# Water_ECMeter-M0.net
KiCad netlist of a schematic drawn in EAGLE
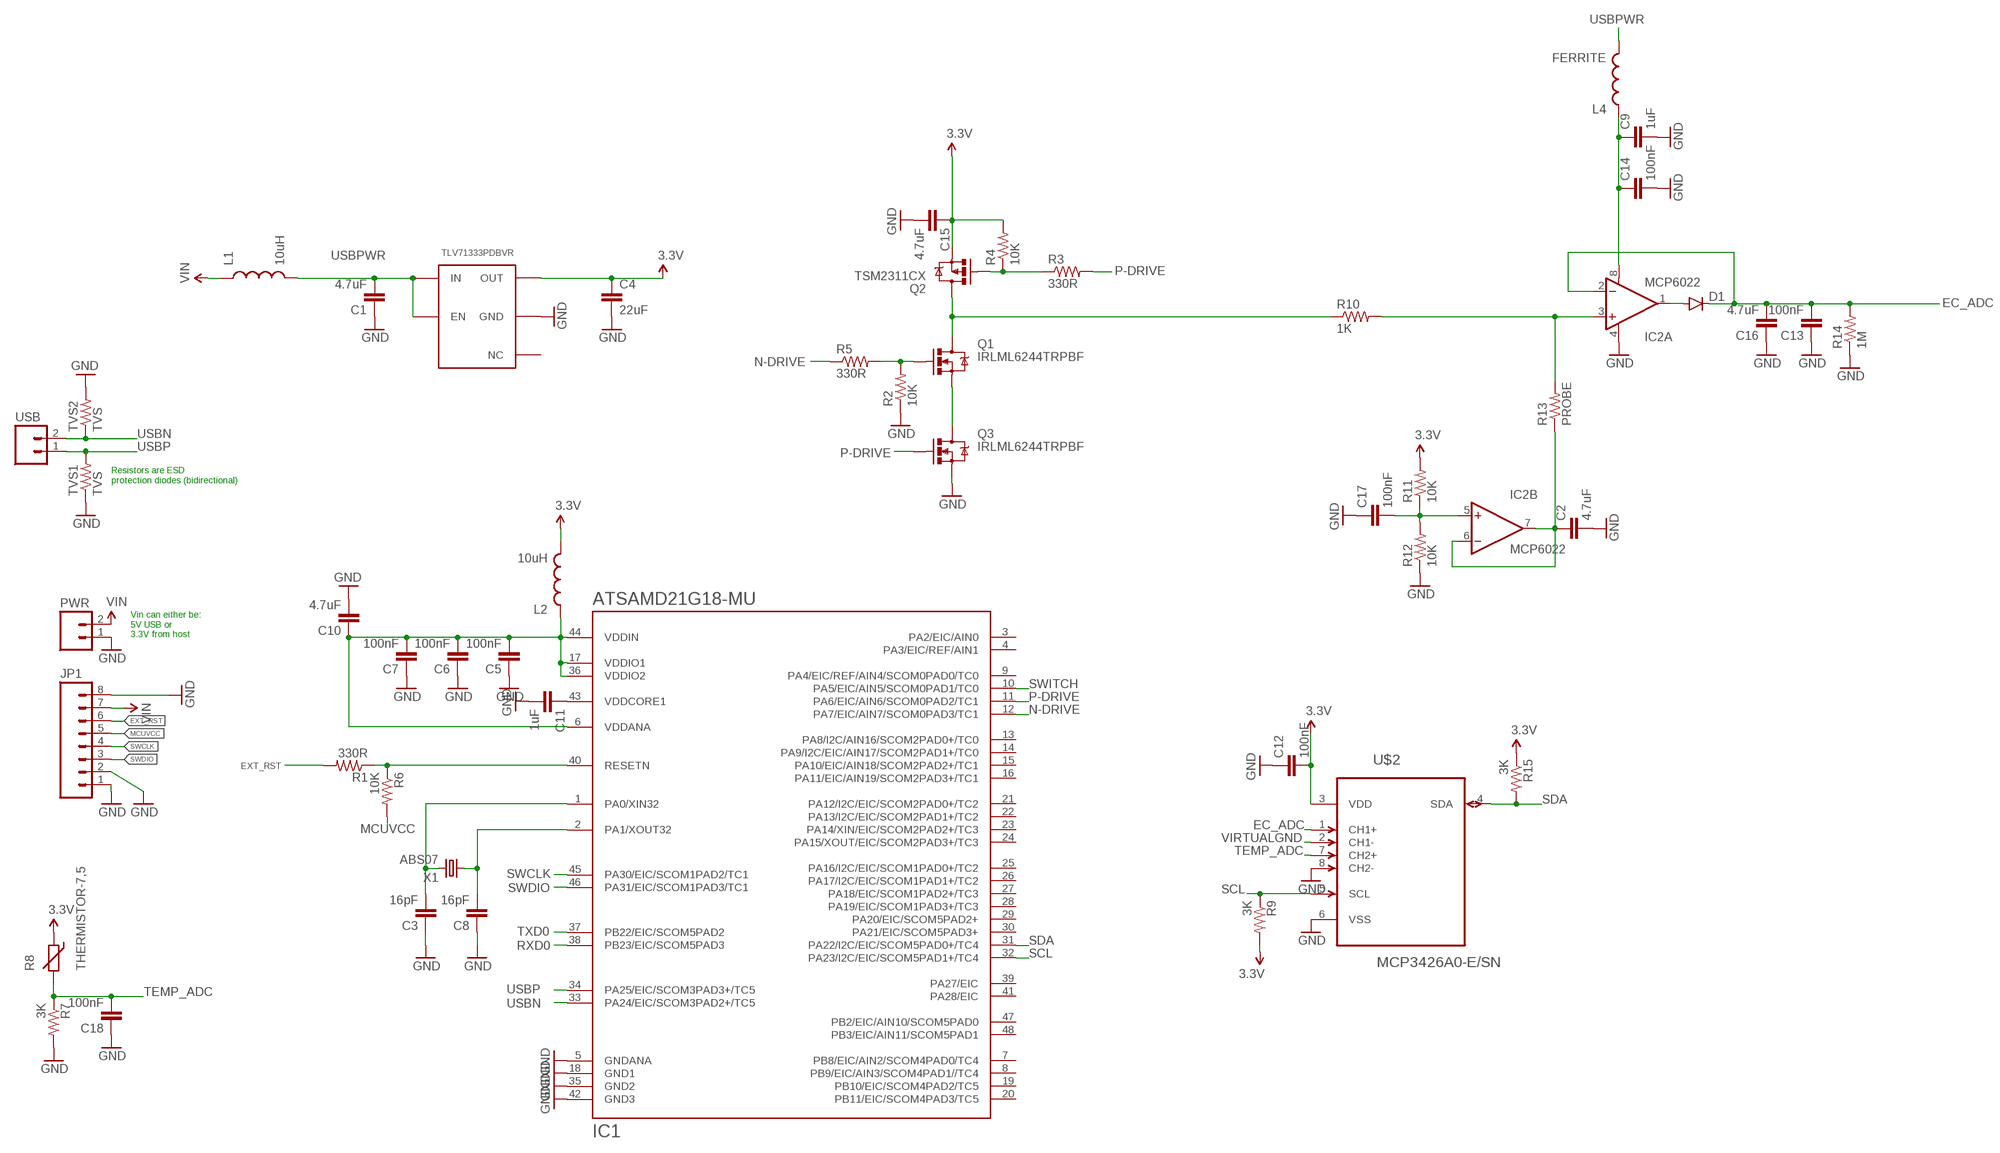
[diagram p0: schematic, sheet 1]

(export (version "E")
  (design (tool "Eeschema 10.0.6"))
  (components
    (comp (ref "C1")
      (value "4.7uF")
      (footprint "eagle-import:0603-CAP")
      (libsource (lib "eagle-import") (part "SparkFun-Passives_CAP0603-CAP"))
    )
    (comp (ref "C2")
      (value "4.7uF")
      (footprint "eagle-import:0603-CAP")
      (libsource (lib "eagle-import") (part "SparkFun-Passives_CAP0603-CAP"))
    )
    (comp (ref "C3")
      (value "16pF")
      (footprint "eagle-import:0402-CAP")
      (libsource (lib "eagle-import") (part "SparkFun-Passives_CAP0402-CAP"))
    )
    (comp (ref "C4")
      (value "22uF")
      (footprint "eagle-import:1206")
      (libsource (lib "eagle-import") (part "CAP1206"))
    )
    (comp (ref "C5")
      (value "100nF")
      (footprint "eagle-import:0402-CAP")
      (libsource (lib "eagle-import") (part "SparkFun-Passives_CAP0402-CAP"))
    )
    (comp (ref "C6")
      (value "100nF")
      (footprint "eagle-import:0402-CAP")
      (libsource (lib "eagle-import") (part "SparkFun-Passives_CAP0402-CAP"))
    )
    (comp (ref "C7")
      (value "100nF")
      (footprint "eagle-import:0402-CAP")
      (libsource (lib "eagle-import") (part "SparkFun-Passives_CAP0402-CAP"))
    )
    (comp (ref "C8")
      (value "16pF")
      (footprint "eagle-import:0402-CAP")
      (libsource (lib "eagle-import") (part "SparkFun-Passives_CAP0402-CAP"))
    )
    (comp (ref "C9")
      (value "1uF")
      (footprint "eagle-import:0402-CAP")
      (libsource (lib "eagle-import") (part "SparkFun-Passives_CAP0402-CAP"))
    )
    (comp (ref "C10")
      (value "4.7uF")
      (footprint "eagle-import:0603-CAP")
      (libsource (lib "eagle-import") (part "SparkFun-Passives_CAP0603-CAP"))
    )
    (comp (ref "C11")
      (value "1uF")
      (footprint "eagle-import:0402-CAP")
      (libsource (lib "eagle-import") (part "SparkFun-Passives_CAP0402-CAP"))
    )
    (comp (ref "C12")
      (value "100nF")
      (footprint "eagle-import:0402-CAP")
      (libsource (lib "eagle-import") (part "SparkFun-Passives_CAP0402-CAP"))
    )
    (comp (ref "C13")
      (value "100nF")
      (footprint "eagle-import:0402-CAP")
      (libsource (lib "eagle-import") (part "SparkFun-Passives_CAP0402-CAP"))
    )
    (comp (ref "C14")
      (value "100nF")
      (footprint "eagle-import:0402-CAP")
      (libsource (lib "eagle-import") (part "SparkFun-Passives_CAP0402-CAP"))
    )
    (comp (ref "C15")
      (value "4.7uF")
      (footprint "eagle-import:0603-CAP")
      (libsource (lib "eagle-import") (part "SparkFun-Passives_CAP0603-CAP"))
    )
    (comp (ref "C16")
      (value "4.7uF")
      (footprint "eagle-import:0603-CAP")
      (libsource (lib "eagle-import") (part "SparkFun-Passives_CAP0603-CAP"))
    )
    (comp (ref "C17")
      (value "100nF")
      (footprint "eagle-import:0402-CAP")
      (libsource (lib "eagle-import") (part "SparkFun-Passives_CAP0402-CAP"))
    )
    (comp (ref "C18")
      (value "100nF")
      (footprint "eagle-import:0402-CAP")
      (libsource (lib "eagle-import") (part "SparkFun-Passives_CAP0402-CAP"))
    )
    (comp (ref "D1")
      (value "DIODESOD123")
      (footprint "eagle-import:SOD-123")
      (libsource (lib "eagle-import") (part "DIODESOD123"))
    )
    (comp (ref "IC1")
      (value "ATSAMD21G18-MU")
      (footprint "eagle-import:QFN48")
      (libsource (lib "eagle-import") (part "ATSAMD21G18-MU"))
    )
    (comp (ref "IC2")
      (value "MCP6022")
      (footprint "eagle-import:SO08")
      (libsource (lib "eagle-import") (part "OPAMP-DUALU"))
    )
    (comp (ref "JP1")
      (value "M08")
      (footprint "eagle-import:1X08_ROUND")
      (libsource (lib "eagle-import") (part "M08"))
    )
    (comp (ref "L1")
      (value "10uH")
      (footprint "eagle-import:0603")
      (libsource (lib "eagle-import") (part "INDUCTOR0603"))
    )
    (comp (ref "L2")
      (value "10uH")
      (footprint "eagle-import:0603")
      (libsource (lib "eagle-import") (part "INDUCTOR0603"))
    )
    (comp (ref "L4")
      (value "FERRITE")
      (footprint "eagle-import:0603")
      (libsource (lib "eagle-import") (part "INDUCTOR0603"))
    )
    (comp (ref "PWR")
      (value "M02LOCK_LONGPADS")
      (footprint "eagle-import:1X02_LOCK_LONGPADS")
      (libsource (lib "eagle-import") (part "M02LOCK_LONGPADS"))
    )
    (comp (ref "Q1")
      (value "IRLML6244TRPBF")
      (footprint "eagle-import:SOT23-3")
      (libsource (lib "eagle-import") (part "MOSFET-NCHANNELAO3404A"))
    )
    (comp (ref "Q2")
      (value "TSM2311CX")
      (footprint "eagle-import:SOT23-3")
      (libsource (lib "eagle-import") (part "MOSFET-PCHANNEL"))
    )
    (comp (ref "Q3")
      (value "IRLML6244TRPBF")
      (footprint "eagle-import:SOT23-3")
      (libsource (lib "eagle-import") (part "MOSFET-NCHANNELAO3404A"))
    )
    (comp (ref "R1")
      (value "330R")
      (footprint "eagle-import:0402-RES")
      (libsource (lib "eagle-import") (part "RESISTOR0402-RES"))
    )
    (comp (ref "R2")
      (value "10K")
      (footprint "eagle-import:0402-RES")
      (libsource (lib "eagle-import") (part "RESISTOR0402-RES"))
    )
    (comp (ref "R3")
      (value "330R")
      (footprint "eagle-import:0402-RES")
      (libsource (lib "eagle-import") (part "RESISTOR0402-RES"))
    )
    (comp (ref "R4")
      (value "10K")
      (footprint "eagle-import:0402-RES")
      (libsource (lib "eagle-import") (part "RESISTOR0402-RES"))
    )
    (comp (ref "R5")
      (value "330R")
      (footprint "eagle-import:0402-RES")
      (libsource (lib "eagle-import") (part "RESISTOR0402-RES"))
    )
    (comp (ref "R6")
      (value "10K")
      (footprint "eagle-import:0402-RES")
      (libsource (lib "eagle-import") (part "RESISTOR0402-RES"))
    )
    (comp (ref "R7")
      (value "3K")
      (footprint "eagle-import:0402-RES")
      (libsource (lib "eagle-import") (part "RESISTOR0402-RES"))
    )
    (comp (ref "R8")
      (value "THERMISTOR-7,5")
      (footprint "eagle-import:R-7,5")
      (libsource (lib "eagle-import") (part "THERMISTOR-7,5"))
    )
    (comp (ref "R9")
      (value "3K")
      (footprint "eagle-import:0402-RES")
      (libsource (lib "eagle-import") (part "RESISTOR0402-RES"))
    )
    (comp (ref "R10")
      (value "1K")
      (footprint "eagle-import:0805")
      (libsource (lib "eagle-import") (part "RESISTOR0805-RES"))
    )
    (comp (ref "R11")
      (value "10K")
      (footprint "eagle-import:0402-RES")
      (libsource (lib "eagle-import") (part "RESISTOR0402-RES"))
    )
    (comp (ref "R12")
      (value "10K")
      (footprint "eagle-import:0402-RES")
      (libsource (lib "eagle-import") (part "RESISTOR0402-RES"))
    )
    (comp (ref "R13")
      (value "PROBE")
      (footprint "eagle-import:AXIAL-0.6")
      (libsource (lib "eagle-import") (part "RESISTORPTH-1W"))
    )
    (comp (ref "R14")
      (value "1M")
      (footprint "eagle-import:0402-RES")
      (libsource (lib "eagle-import") (part "RESISTOR0402-RES"))
    )
    (comp (ref "R15")
      (value "3K")
      (footprint "eagle-import:0402-RES")
      (libsource (lib "eagle-import") (part "RESISTOR0402-RES"))
    )
    (comp (ref "TVS1")
      (value "TVS")
      (footprint "eagle-import:0402-RES")
      (libsource (lib "eagle-import") (part "RESISTOR0402-RES"))
    )
    (comp (ref "TVS2")
      (value "TVS")
      (footprint "eagle-import:0402-RES")
      (libsource (lib "eagle-import") (part "RESISTOR0402-RES"))
    )
    (comp (ref "U$1")
      (value "TLV71333PDBVR")
      (footprint "eagle-import:TLV71333PDBVR")
      (libsource (lib "eagle-import") (part "TLV71333PDBVR"))
    )
    (comp (ref "U$2")
      (value "MCP3426A0-E/SN")
      (footprint "eagle-import:SOIC127P600X175-8N")
      (libsource (lib "eagle-import") (part "MCP3426A0-E/SN"))
    )
    (comp (ref "USB")
      (value "M02LOCK_LONGPADS")
      (footprint "eagle-import:1X02_LOCK_LONGPADS")
      (libsource (lib "eagle-import") (part "M02LOCK_LONGPADS"))
    )
    (comp (ref "X1")
      (value "ABS07")
      (footprint "eagle-import:ABS07")
      (libsource (lib "eagle-import") (part "ABS07"))
    )
  )
  (nets
    (net (code "1") (name "/EC_ADC") (class "Default")
      (node (ref "C13") (pin "2") (pinfunction "2_2") (pintype "passive"))
      (node (ref "C16") (pin "2") (pinfunction "2_2") (pintype "passive"))
      (node (ref "D1") (pin "C") (pinfunction "C_C") (pintype "passive"))
      (node (ref "IC2") (pin "2") (pinfunction "-IN_2") (pintype "input"))
      (node (ref "R14") (pin "2") (pinfunction "2_2") (pintype "passive"))
      (node (ref "U$2") (pin "1") (pinfunction "CH1+_1") (pintype "input"))
    )
    (net (code "2") (name "/N-DRIVE") (class "Default")
      (node (ref "IC1") (pin "12") (pinfunction "PA7/EIC/AIN7/SCOM0PAD3/TC1_12") (pintype "bidirectional"))
      (node (ref "R5") (pin "1") (pinfunction "1_1") (pintype "passive"))
    )
    (net (code "3") (name "/P-DRIVE") (class "Default")
      (node (ref "IC1") (pin "11") (pinfunction "PA6/EIC/AIN6/SCOM0PAD2/TC1_11") (pintype "bidirectional"))
      (node (ref "Q3") (pin "1") (pinfunction "G_1") (pintype "passive"))
      (node (ref "R3") (pin "2") (pinfunction "2_2") (pintype "passive"))
    )
    (net (code "4") (name "/RXD0") (class "Default")
      (node (ref "IC1") (pin "38") (pinfunction "PB23/EIC/SCOM5PAD3_38") (pintype "bidirectional"))
    )
    (net (code "5") (name "/SCL") (class "Default")
      (node (ref "IC1") (pin "32") (pinfunction "PA23/I2C/EIC/SCOM5PAD1+/TC4_32") (pintype "bidirectional"))
      (node (ref "R9") (pin "1") (pinfunction "1_1") (pintype "passive"))
      (node (ref "U$2") (pin "5") (pinfunction "SCL_5") (pintype "input"))
    )
    (net (code "6") (name "/SDA") (class "Default")
      (node (ref "IC1") (pin "31") (pinfunction "PA22/I2C/EIC/SCOM5PAD0+/TC4_31") (pintype "bidirectional"))
      (node (ref "R15") (pin "2") (pinfunction "2_2") (pintype "passive"))
      (node (ref "U$2") (pin "4") (pinfunction "SDA_4") (pintype "bidirectional"))
    )
    (net (code "7") (name "/SWITCH") (class "Default")
      (node (ref "IC1") (pin "10") (pinfunction "PA5/EIC/AIN5/SCOM0PAD1/TC0_10") (pintype "bidirectional"))
    )
    (net (code "8") (name "/TEMP_ADC") (class "Default")
      (node (ref "C18") (pin "2") (pinfunction "2_2") (pintype "passive"))
      (node (ref "R7") (pin "1") (pinfunction "1_1") (pintype "passive"))
      (node (ref "R8") (pin "2") (pinfunction "2_2") (pintype "passive"))
      (node (ref "U$2") (pin "7") (pinfunction "CH2+_7") (pintype "input"))
    )
    (net (code "9") (name "/TXD0") (class "Default")
      (node (ref "IC1") (pin "37") (pinfunction "PB22/EIC/SCOM5PAD2_37") (pintype "bidirectional"))
    )
    (net (code "10") (name "/USBN") (class "Default")
      (node (ref "IC1") (pin "33") (pinfunction "PA24/EIC/SCOM3PAD2+/TC5_33") (pintype "bidirectional"))
      (node (ref "TVS2") (pin "1") (pinfunction "1_1") (pintype "passive"))
      (node (ref "USB") (pin "2") (pinfunction "2_2") (pintype "passive"))
    )
    (net (code "11") (name "/USBP") (class "Default")
      (node (ref "IC1") (pin "34") (pinfunction "PA25/EIC/SCOM3PAD3+/TC5_34") (pintype "bidirectional"))
      (node (ref "TVS1") (pin "2") (pinfunction "2_2") (pintype "passive"))
      (node (ref "USB") (pin "1") (pinfunction "1_1") (pintype "passive"))
    )
    (net (code "12") (name "/USBPWR") (class "Default")
      (node (ref "C1") (pin "2") (pinfunction "2_2") (pintype "passive"))
      (node (ref "L1") (pin "2") (pinfunction "2_2") (pintype "passive"))
      (node (ref "L4") (pin "2") (pinfunction "2_2") (pintype "passive"))
      (node (ref "U$1") (pin "P$1") (pinfunction "IN_P$1") (pintype "bidirectional"))
      (node (ref "U$1") (pin "P$3") (pinfunction "EN_P$3") (pintype "bidirectional"))
    )
    (net (code "13") (name "/VIRTUALGND") (class "Default")
      (node (ref "C2") (pin "1") (pinfunction "1_1") (pintype "passive"))
      (node (ref "IC2") (pin "6") (pinfunction "-IN_6") (pintype "input"))
      (node (ref "IC2") (pin "7") (pinfunction "OUT_7") (pintype "output"))
      (node (ref "R13") (pin "P$1") (pinfunction "1_P$1") (pintype "passive"))
      (node (ref "U$2") (pin "2") (pinfunction "CH1-_2") (pintype "input"))
    )
    (net (code "14") (name "3.3V") (class "Default")
      (node (ref "C12") (pin "2") (pinfunction "2_2") (pintype "passive"))
      (node (ref "C15") (pin "1") (pinfunction "1_1") (pintype "passive"))
      (node (ref "C4") (pin "1") (pinfunction "1_1") (pintype "passive"))
      (node (ref "L2") (pin "2") (pinfunction "2_2") (pintype "passive"))
      (node (ref "Q2") (pin "2") (pinfunction "S_2") (pintype "passive"))
      (node (ref "R11") (pin "2") (pinfunction "2_2") (pintype "passive"))
      (node (ref "R15") (pin "1") (pinfunction "1_1") (pintype "passive"))
      (node (ref "R4") (pin "2") (pinfunction "2_2") (pintype "passive"))
      (node (ref "R8") (pin "1") (pinfunction "1_1") (pintype "passive"))
      (node (ref "R9") (pin "2") (pinfunction "2_2") (pintype "passive"))
      (node (ref "U$1") (pin "P$5") (pinfunction "OUT_P$5") (pintype "bidirectional"))
      (node (ref "U$2") (pin "3") (pinfunction "VDD_3") (pintype "power_in"))
    )
    (net (code "15") (name "EXT_RST") (class "Default")
      (node (ref "JP1") (pin "6") (pinfunction "6_6") (pintype "passive"))
      (node (ref "R1") (pin "2") (pinfunction "2_2") (pintype "passive"))
    )
    (net (code "16") (name "GND") (class "Default")
      (node (ref "C1") (pin "1") (pinfunction "1_1") (pintype "passive"))
      (node (ref "C10") (pin "2") (pinfunction "2_2") (pintype "passive"))
      (node (ref "C11") (pin "2") (pinfunction "2_2") (pintype "passive"))
      (node (ref "C12") (pin "1") (pinfunction "1_1") (pintype "passive"))
      (node (ref "C13") (pin "1") (pinfunction "1_1") (pintype "passive"))
      (node (ref "C14") (pin "2") (pinfunction "2_2") (pintype "passive"))
      (node (ref "C15") (pin "2") (pinfunction "2_2") (pintype "passive"))
      (node (ref "C16") (pin "1") (pinfunction "1_1") (pintype "passive"))
      (node (ref "C17") (pin "1") (pinfunction "1_1") (pintype "passive"))
      (node (ref "C18") (pin "1") (pinfunction "1_1") (pintype "passive"))
      (node (ref "C2") (pin "2") (pinfunction "2_2") (pintype "passive"))
      (node (ref "C3") (pin "1") (pinfunction "1_1") (pintype "passive"))
      (node (ref "C4") (pin "2") (pinfunction "2_2") (pintype "passive"))
      (node (ref "C5") (pin "1") (pinfunction "1_1") (pintype "passive"))
      (node (ref "C6") (pin "1") (pinfunction "1_1") (pintype "passive"))
      (node (ref "C7") (pin "1") (pinfunction "1_1") (pintype "passive"))
      (node (ref "C8") (pin "1") (pinfunction "1_1") (pintype "passive"))
      (node (ref "C9") (pin "2") (pinfunction "2_2") (pintype "passive"))
      (node (ref "IC1") (pin "18") (pinfunction "GND1_18") (pintype "power_in"))
      (node (ref "IC1") (pin "35") (pinfunction "GND2_35") (pintype "power_in"))
      (node (ref "IC1") (pin "42") (pinfunction "GND3_42") (pintype "power_in"))
      (node (ref "IC1") (pin "5") (pinfunction "GNDANA_5") (pintype "power_in"))
      (node (ref "IC2") (pin "4") (pinfunction "V-_4") (pintype "power_in"))
      (node (ref "JP1") (pin "1") (pinfunction "1_1") (pintype "passive"))
      (node (ref "JP1") (pin "2") (pinfunction "2_2") (pintype "passive"))
      (node (ref "JP1") (pin "8") (pinfunction "8_8") (pintype "passive"))
      (node (ref "PWR") (pin "1") (pinfunction "1_1") (pintype "passive"))
      (node (ref "Q3") (pin "2") (pinfunction "S_2") (pintype "passive"))
      (node (ref "R12") (pin "1") (pinfunction "1_1") (pintype "passive"))
      (node (ref "R14") (pin "1") (pinfunction "1_1") (pintype "passive"))
      (node (ref "R2") (pin "1") (pinfunction "1_1") (pintype "passive"))
      (node (ref "R7") (pin "2") (pinfunction "2_2") (pintype "passive"))
      (node (ref "TVS1") (pin "1") (pinfunction "1_1") (pintype "passive"))
      (node (ref "TVS2") (pin "2") (pinfunction "2_2") (pintype "passive"))
      (node (ref "U$1") (pin "P$2") (pinfunction "GND_P$2") (pintype "bidirectional"))
      (node (ref "U$2") (pin "6") (pinfunction "VSS_6") (pintype "power_in"))
      (node (ref "U$2") (pin "8") (pinfunction "CH2-_8") (pintype "input"))
    )
    (net (code "17") (name "MCUVCC") (class "Default")
      (node (ref "C10") (pin "1") (pinfunction "1_1") (pintype "passive"))
      (node (ref "C5") (pin "2") (pinfunction "2_2") (pintype "passive"))
      (node (ref "C6") (pin "2") (pinfunction "2_2") (pintype "passive"))
      (node (ref "C7") (pin "2") (pinfunction "2_2") (pintype "passive"))
      (node (ref "IC1") (pin "17") (pinfunction "VDDIO1_17") (pintype "power_in"))
      (node (ref "IC1") (pin "36") (pinfunction "VDDIO2_36") (pintype "power_in"))
      (node (ref "IC1") (pin "44") (pinfunction "VDDIN_44") (pintype "power_in"))
      (node (ref "IC1") (pin "6") (pinfunction "VDDANA_6") (pintype "power_in"))
      (node (ref "JP1") (pin "5") (pinfunction "5_5") (pintype "passive"))
      (node (ref "L2") (pin "1") (pinfunction "1_1") (pintype "passive"))
      (node (ref "R6") (pin "2") (pinfunction "2_2") (pintype "passive"))
    )
    (net (code "18") (name "Net-(IC1-PA0{slash}XIN32)") (class "Default")
      (node (ref "C3") (pin "2") (pinfunction "2_2") (pintype "passive"))
      (node (ref "IC1") (pin "1") (pinfunction "PA0/XIN32_1") (pintype "bidirectional"))
      (node (ref "X1") (pin "P$2") (pinfunction "2_P$2") (pintype "passive"))
    )
    (net (code "19") (name "Net-(IC1-PA1{slash}XOUT32)") (class "Default")
      (node (ref "C8") (pin "2") (pinfunction "2_2") (pintype "passive"))
      (node (ref "IC1") (pin "2") (pinfunction "PA1/XOUT32_2") (pintype "bidirectional"))
      (node (ref "X1") (pin "P$1") (pinfunction "1_P$1") (pintype "passive"))
    )
    (net (code "20") (name "Net-(IC1-RESETN)") (class "Default")
      (node (ref "IC1") (pin "40") (pinfunction "RESETN_40") (pintype "bidirectional"))
      (node (ref "R1") (pin "1") (pinfunction "1_1") (pintype "passive"))
      (node (ref "R6") (pin "1") (pinfunction "1_1") (pintype "passive"))
    )
    (net (code "21") (name "Net-(IC1-VDDCORE1)") (class "Default")
      (node (ref "C11") (pin "1") (pinfunction "1_1") (pintype "passive"))
      (node (ref "IC1") (pin "43") (pinfunction "VDDCORE1_43") (pintype "input"))
    )
    (net (code "22") (name "Net-(IC2A-+IN)") (class "Default")
      (node (ref "IC2") (pin "3") (pinfunction "+IN_3") (pintype "input"))
      (node (ref "R10") (pin "2") (pinfunction "2_2") (pintype "passive"))
      (node (ref "R13") (pin "P$2") (pinfunction "2_P$2") (pintype "passive"))
    )
    (net (code "23") (name "Net-(IC2A-OUT)") (class "Default")
      (node (ref "D1") (pin "A") (pinfunction "A_A") (pintype "passive"))
      (node (ref "IC2") (pin "1") (pinfunction "OUT_1") (pintype "output"))
    )
    (net (code "24") (name "Net-(IC2A-V+)") (class "Default")
      (node (ref "C14") (pin "1") (pinfunction "1_1") (pintype "passive"))
      (node (ref "C9") (pin "1") (pinfunction "1_1") (pintype "passive"))
      (node (ref "IC2") (pin "8") (pinfunction "V+_8") (pintype "power_in"))
      (node (ref "L4") (pin "1") (pinfunction "1_1") (pintype "passive"))
    )
    (net (code "25") (name "Net-(IC2B-+IN)") (class "Default")
      (node (ref "C17") (pin "2") (pinfunction "2_2") (pintype "passive"))
      (node (ref "IC2") (pin "5") (pinfunction "+IN_5") (pintype "input"))
      (node (ref "R11") (pin "1") (pinfunction "1_1") (pintype "passive"))
      (node (ref "R12") (pin "2") (pinfunction "2_2") (pintype "passive"))
    )
    (net (code "26") (name "Net-(Q1-D)") (class "Default")
      (node (ref "Q1") (pin "3") (pinfunction "D_3") (pintype "passive"))
      (node (ref "Q2") (pin "3") (pinfunction "D_3") (pintype "passive"))
      (node (ref "R10") (pin "1") (pinfunction "1_1") (pintype "passive"))
    )
    (net (code "27") (name "Net-(Q1-G)") (class "Default")
      (node (ref "Q1") (pin "1") (pinfunction "G_1") (pintype "passive"))
      (node (ref "R2") (pin "2") (pinfunction "2_2") (pintype "passive"))
      (node (ref "R5") (pin "2") (pinfunction "2_2") (pintype "passive"))
    )
    (net (code "28") (name "Net-(Q1-S)") (class "Default")
      (node (ref "Q1") (pin "2") (pinfunction "S_2") (pintype "passive"))
      (node (ref "Q3") (pin "3") (pinfunction "D_3") (pintype "passive"))
    )
    (net (code "29") (name "Net-(Q2-G)") (class "Default")
      (node (ref "Q2") (pin "1") (pinfunction "G_1") (pintype "passive"))
      (node (ref "R3") (pin "1") (pinfunction "1_1") (pintype "passive"))
      (node (ref "R4") (pin "1") (pinfunction "1_1") (pintype "passive"))
    )
    (net (code "30") (name "SWCLK") (class "Default")
      (node (ref "IC1") (pin "45") (pinfunction "PA30/EIC/SCOM1PAD2/TC1_45") (pintype "bidirectional"))
      (node (ref "JP1") (pin "4") (pinfunction "4_4") (pintype "passive"))
    )
    (net (code "31") (name "SWDIO") (class "Default")
      (node (ref "IC1") (pin "46") (pinfunction "PA31/EIC/SCOM1PAD3/TC1_46") (pintype "bidirectional"))
      (node (ref "JP1") (pin "3") (pinfunction "3_3") (pintype "passive"))
    )
    (net (code "32") (name "VIN") (class "Default")
      (node (ref "JP1") (pin "7") (pinfunction "7_7") (pintype "passive"))
      (node (ref "L1") (pin "1") (pinfunction "1_1") (pintype "passive"))
      (node (ref "PWR") (pin "2") (pinfunction "2_2") (pintype "passive"))
    )
    (net (code "33") (name "unconnected-(IC1-PA2{slash}EIC{slash}AIN0-Pad3)") (class "Default")
      (node (ref "IC1") (pin "3") (pinfunction "PA2/EIC/AIN0_3") (pintype "bidirectional"))
    )
    (net (code "34") (name "unconnected-(IC1-PA3{slash}EIC{slash}REF{slash}AIN1-Pad4)") (class "Default")
      (node (ref "IC1") (pin "4") (pinfunction "PA3/EIC/REF/AIN1_4") (pintype "bidirectional"))
    )
    (net (code "35") (name "unconnected-(IC1-PA4{slash}EIC{slash}REF{slash}AIN4{slash}SCOM0PAD0{slash}TC0-Pad9)") (class "Default")
      (node (ref "IC1") (pin "9") (pinfunction "PA4/EIC/REF/AIN4/SCOM0PAD0/TC0_9") (pintype "bidirectional"))
    )
    (net (code "36") (name "unconnected-(IC1-PA8{slash}I2C{slash}AIN16{slash}SCOM2PAD0+{slash}TC0-Pad13)") (class "Default")
      (node (ref "IC1") (pin "13") (pinfunction "PA8/I2C/AIN16/SCOM2PAD0+/TC0_13") (pintype "bidirectional"))
    )
    (net (code "37") (name "unconnected-(IC1-PA9{slash}I2C{slash}EIC{slash}AIN17{slash}SCOM2PAD1+{slash}TC0-Pad14)") (class "Default")
      (node (ref "IC1") (pin "14") (pinfunction "PA9/I2C/EIC/AIN17/SCOM2PAD1+/TC0_14") (pintype "bidirectional"))
    )
    (net (code "38") (name "unconnected-(IC1-PA10{slash}EIC{slash}AIN18{slash}SCOM2PAD2+{slash}TC1-Pad15)") (class "Default")
      (node (ref "IC1") (pin "15") (pinfunction "PA10/EIC/AIN18/SCOM2PAD2+/TC1_15") (pintype "bidirectional"))
    )
    (net (code "39") (name "unconnected-(IC1-PA11{slash}EIC{slash}AIN19{slash}SCOM2PAD3+{slash}TC1-Pad16)") (class "Default")
      (node (ref "IC1") (pin "16") (pinfunction "PA11/EIC/AIN19/SCOM2PAD3+/TC1_16") (pintype "bidirectional"))
    )
    (net (code "40") (name "unconnected-(IC1-PA12{slash}I2C{slash}EIC{slash}SCOM2PAD0+{slash}TC2-Pad21)") (class "Default")
      (node (ref "IC1") (pin "21") (pinfunction "PA12/I2C/EIC/SCOM2PAD0+/TC2_21") (pintype "bidirectional"))
    )
    (net (code "41") (name "unconnected-(IC1-PA13{slash}I2C{slash}EIC{slash}SCOM2PAD1+{slash}TC2-Pad22)") (class "Default")
      (node (ref "IC1") (pin "22") (pinfunction "PA13/I2C/EIC/SCOM2PAD1+/TC2_22") (pintype "bidirectional"))
    )
    (net (code "42") (name "unconnected-(IC1-PA14{slash}XIN{slash}EIC{slash}SCOM2PAD2+{slash}TC3-Pad23)") (class "Default")
      (node (ref "IC1") (pin "23") (pinfunction "PA14/XIN/EIC/SCOM2PAD2+/TC3_23") (pintype "bidirectional"))
    )
    (net (code "43") (name "unconnected-(IC1-PA15{slash}XOUT{slash}EIC{slash}SCOM2PAD3+{slash}TC3-Pad24)") (class "Default")
      (node (ref "IC1") (pin "24") (pinfunction "PA15/XOUT/EIC/SCOM2PAD3+/TC3_24") (pintype "bidirectional"))
    )
    (net (code "44") (name "unconnected-(IC1-PA16{slash}I2C{slash}EIC{slash}SCOM1PAD0+{slash}TC2-Pad25)") (class "Default")
      (node (ref "IC1") (pin "25") (pinfunction "PA16/I2C/EIC/SCOM1PAD0+/TC2_25") (pintype "bidirectional"))
    )
    (net (code "45") (name "unconnected-(IC1-PA17{slash}I2C{slash}EIC{slash}SCOM1PAD1+{slash}TC2-Pad26)") (class "Default")
      (node (ref "IC1") (pin "26") (pinfunction "PA17/I2C/EIC/SCOM1PAD1+/TC2_26") (pintype "bidirectional"))
    )
    (net (code "46") (name "unconnected-(IC1-PA18{slash}EIC{slash}SCOM1PAD2+{slash}TC3-Pad27)") (class "Default")
      (node (ref "IC1") (pin "27") (pinfunction "PA18/EIC/SCOM1PAD2+/TC3_27") (pintype "bidirectional"))
    )
    (net (code "47") (name "unconnected-(IC1-PA19{slash}EIC{slash}SCOM1PAD3+{slash}TC3-Pad28)") (class "Default")
      (node (ref "IC1") (pin "28") (pinfunction "PA19/EIC/SCOM1PAD3+/TC3_28") (pintype "bidirectional"))
    )
    (net (code "48") (name "unconnected-(IC1-PA20{slash}EIC{slash}SCOM5PAD2+-Pad29)") (class "Default")
      (node (ref "IC1") (pin "29") (pinfunction "PA20/EIC/SCOM5PAD2+_29") (pintype "bidirectional"))
    )
    (net (code "49") (name "unconnected-(IC1-PA21{slash}EIC{slash}SCOM5PAD3+-Pad30)") (class "Default")
      (node (ref "IC1") (pin "30") (pinfunction "PA21/EIC/SCOM5PAD3+_30") (pintype "bidirectional"))
    )
    (net (code "50") (name "unconnected-(IC1-PA27{slash}EIC-Pad39)") (class "Default")
      (node (ref "IC1") (pin "39") (pinfunction "PA27/EIC_39") (pintype "bidirectional"))
    )
    (net (code "51") (name "unconnected-(IC1-PA28{slash}EIC-Pad41)") (class "Default")
      (node (ref "IC1") (pin "41") (pinfunction "PA28/EIC_41") (pintype "bidirectional"))
    )
    (net (code "52") (name "unconnected-(IC1-PB2{slash}EIC{slash}AIN10{slash}SCOM5PAD0-Pad47)") (class "Default")
      (node (ref "IC1") (pin "47") (pinfunction "PB2/EIC/AIN10/SCOM5PAD0_47") (pintype "bidirectional"))
    )
    (net (code "53") (name "unconnected-(IC1-PB3{slash}EIC{slash}AIN11{slash}SCOM5PAD1-Pad48)") (class "Default")
      (node (ref "IC1") (pin "48") (pinfunction "PB3/EIC/AIN11/SCOM5PAD1_48") (pintype "bidirectional"))
    )
    (net (code "54") (name "unconnected-(IC1-PB8{slash}EIC{slash}AIN2{slash}SCOM4PAD0{slash}TC4-Pad7)") (class "Default")
      (node (ref "IC1") (pin "7") (pinfunction "PB8/EIC/AIN2/SCOM4PAD0/TC4_7") (pintype "bidirectional"))
    )
    (net (code "55") (name "unconnected-(IC1-PB9{slash}EIC{slash}AIN3{slash}SCOM4PAD1{slash}{slash}TC4-Pad8)") (class "Default")
      (node (ref "IC1") (pin "8") (pinfunction "PB9/EIC/AIN3/SCOM4PAD1//TC4_8") (pintype "bidirectional"))
    )
    (net (code "56") (name "unconnected-(IC1-PB10{slash}EIC{slash}SCOM4PAD2{slash}TC5-Pad19)") (class "Default")
      (node (ref "IC1") (pin "19") (pinfunction "PB10/EIC/SCOM4PAD2/TC5_19") (pintype "bidirectional"))
    )
    (net (code "57") (name "unconnected-(IC1-PB11{slash}EIC{slash}SCOM4PAD3{slash}TC5-Pad20)") (class "Default")
      (node (ref "IC1") (pin "20") (pinfunction "PB11/EIC/SCOM4PAD3/TC5_20") (pintype "bidirectional"))
    )
    (net (code "58") (name "unconnected-(U$1-NC-PadP$4)") (class "Default")
      (node (ref "U$1") (pin "P$4") (pinfunction "NC_P$4") (pintype "bidirectional"))
    )
  )
)
